# Breadboard_Power_Supply_-_SMD.net
KiCad netlist of a schematic drawn in EAGLE
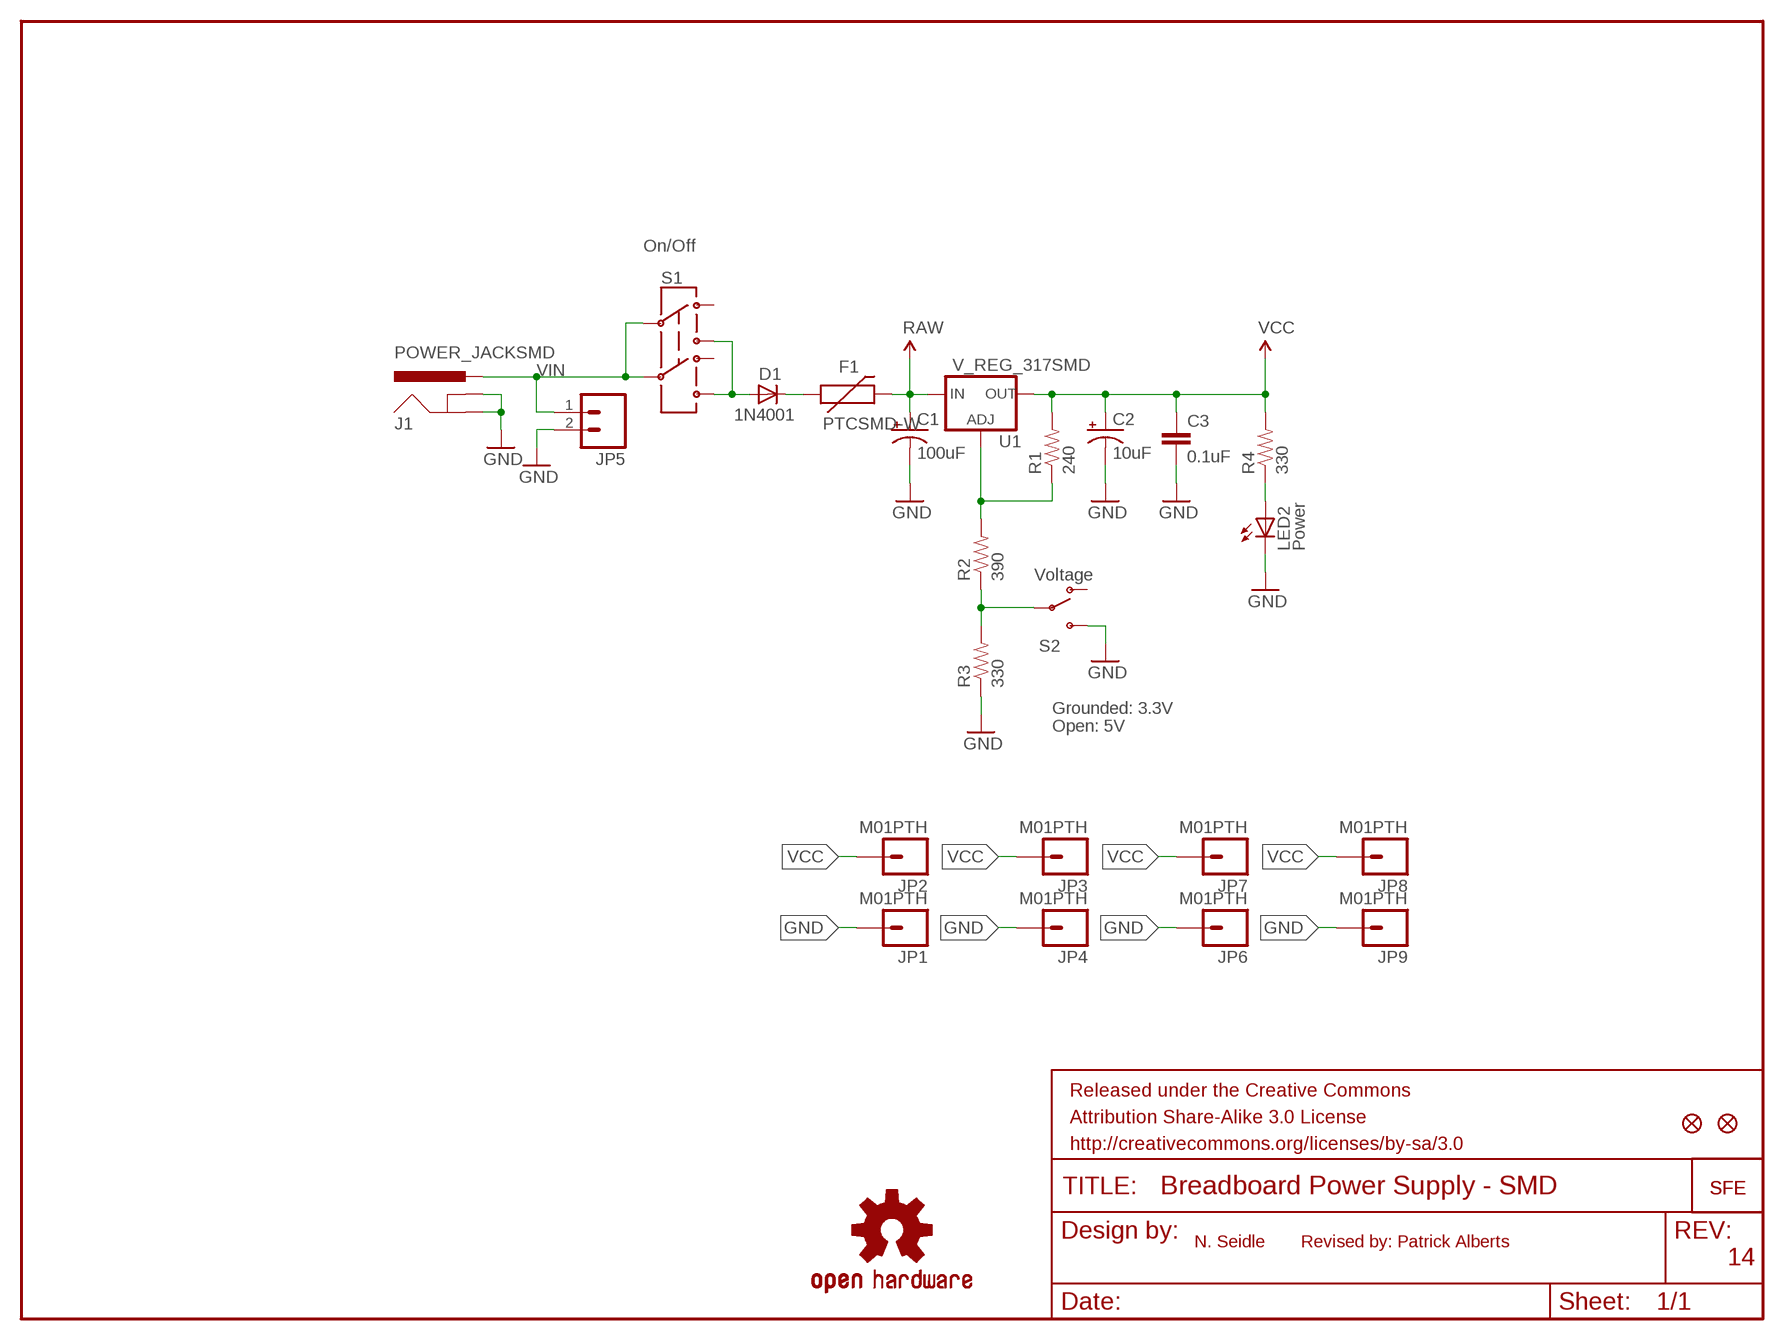
[diagram p0: schematic, sheet 1]

(export (version "E")
  (design (tool "Eeschema 10.0.6"))
  (components
    (comp (ref "C1")
      (value "100uF")
      (footprint "eagle-import:EIA7343")
      (libsource (lib "eagle-import") (part "CAP_POL7343"))
    )
    (comp (ref "C2")
      (value "10uF")
      (footprint "eagle-import:EIA3216")
      (libsource (lib "eagle-import") (part "CAP_POL1206"))
    )
    (comp (ref "C3")
      (value "0.1uF")
      (footprint "eagle-import:0603-CAP")
      (libsource (lib "eagle-import") (part "CAP0603-CAP"))
    )
    (comp (ref "D1")
      (value "1N4001")
      (footprint "eagle-import:SMA-DIODE-TYLERALT1")
      (libsource (lib "eagle-import") (part "DIODESMA-TYLERALT1"))
    )
    (comp (ref "F1")
      (value "PTCSMD-W")
      (footprint "eagle-import:PTC-1206-WIDE")
      (libsource (lib "eagle-import") (part "PTCSMD-W"))
    )
    (comp (ref "FRAME1")
      (value "FRAME-LETTER")
      (footprint "eagle-import:CREATIVE_COMMONS")
      (libsource (lib "eagle-import") (part "FRAME-LETTER"))
    )
    (comp (ref "J1")
      (value "POWER_JACKSMD")
      (footprint "eagle-import:POWER_JACK_SMD")
      (libsource (lib "eagle-import") (part "POWER_JACKSMD"))
    )
    (comp (ref "JP1")
      (value "M01PTH")
      (footprint "eagle-import:1X01")
      (libsource (lib "eagle-import") (part "M01PTH"))
    )
    (comp (ref "JP2")
      (value "M01PTH")
      (footprint "eagle-import:1X01")
      (libsource (lib "eagle-import") (part "M01PTH"))
    )
    (comp (ref "JP3")
      (value "M01PTH")
      (footprint "eagle-import:1X01")
      (libsource (lib "eagle-import") (part "M01PTH"))
    )
    (comp (ref "JP4")
      (value "M01PTH")
      (footprint "eagle-import:1X01")
      (libsource (lib "eagle-import") (part "M01PTH"))
    )
    (comp (ref "JP5")
      (value "M02PTH")
      (footprint "eagle-import:1X02")
      (libsource (lib "eagle-import") (part "M02PTH"))
    )
    (comp (ref "JP6")
      (value "M01PTH")
      (footprint "eagle-import:1X01")
      (libsource (lib "eagle-import") (part "M01PTH"))
    )
    (comp (ref "JP7")
      (value "M01PTH")
      (footprint "eagle-import:1X01")
      (libsource (lib "eagle-import") (part "M01PTH"))
    )
    (comp (ref "JP8")
      (value "M01PTH")
      (footprint "eagle-import:1X01")
      (libsource (lib "eagle-import") (part "M01PTH"))
    )
    (comp (ref "JP9")
      (value "M01PTH")
      (footprint "eagle-import:1X01")
      (libsource (lib "eagle-import") (part "M01PTH"))
    )
    (comp (ref "LED2")
      (value "Power")
      (footprint "eagle-import:LED-1206")
      (libsource (lib "eagle-import") (part "LED1206"))
    )
    (comp (ref "LOGO1")
      (value "OSHW-LOGOS")
      (footprint "eagle-import:OSHW-LOGO-S")
      (libsource (lib "eagle-import") (part "OSHW-LOGOS"))
    )
    (comp (ref "R1")
      (value "240")
      (footprint "eagle-import:0603-RES")
      (libsource (lib "eagle-import") (part "RESISTOR0603-RES"))
    )
    (comp (ref "R2")
      (value "390")
      (footprint "eagle-import:0603-RES")
      (libsource (lib "eagle-import") (part "RESISTOR0603-RES"))
    )
    (comp (ref "R3")
      (value "330")
      (footprint "eagle-import:0603-RES")
      (libsource (lib "eagle-import") (part "RESISTOR0603-RES"))
    )
    (comp (ref "R4")
      (value "330")
      (footprint "eagle-import:0603-RES")
      (libsource (lib "eagle-import") (part "RESISTOR0603-RES"))
    )
    (comp (ref "S1")
      (value "On/Off")
      (footprint "eagle-import:AYZ0202")
      (libsource (lib "eagle-import") (part "AYZ0202"))
    )
    (comp (ref "S2")
      (value "Voltage")
      (footprint "eagle-import:AYZ0202")
      (libsource (lib "eagle-import") (part "SWITCH-SPSTSMD"))
    )
    (comp (ref "U$1")
      (value "LOGO-SFESK")
      (footprint "eagle-import:SFE-LOGO-FLAME")
      (libsource (lib "eagle-import") (part "LOGO-SFESK"))
    )
    (comp (ref "U$2")
      (value "LOGO-SFENEW")
      (footprint "eagle-import:SFE-NEW-WEBLOGO")
      (libsource (lib "eagle-import") (part "LOGO-SFENEW"))
    )
    (comp (ref "U$3")
      (value "FIDUCIAL1X2")
      (footprint "eagle-import:FIDUCIAL-1X2")
      (libsource (lib "eagle-import") (part "FIDUCIAL1X2"))
    )
    (comp (ref "U$4")
      (value "FIDUCIAL1X2")
      (footprint "eagle-import:FIDUCIAL-1X2")
      (libsource (lib "eagle-import") (part "FIDUCIAL1X2"))
    )
    (comp (ref "U1")
      (value "V_REG_317SMD")
      (footprint "eagle-import:SOT223")
      (libsource (lib "eagle-import") (part "V_REG_317SMD"))
    )
  )
  (nets
    (net (code "1") (name "/VIN") (class "Default")
      (node (ref "J1") (pin "VIN0") (pinfunction "PWR_VIN0") (pintype "bidirectional"))
      (node (ref "JP5") (pin "1") (pinfunction "1_1") (pintype "passive"))
      (node (ref "S1") (pin "2") (pinfunction "2_2") (pintype "bidirectional"))
      (node (ref "S1") (pin "5") (pinfunction "5_5") (pintype "bidirectional"))
    )
    (net (code "2") (name "GND") (class "Default")
      (node (ref "C1") (pin "C") (pinfunction "-_C") (pintype "passive"))
      (node (ref "C2") (pin "C") (pinfunction "-_C") (pintype "passive"))
      (node (ref "C3") (pin "2") (pinfunction "2_2") (pintype "passive"))
      (node (ref "J1") (pin "GND") (pinfunction "GNDBREAK_GND") (pintype "bidirectional"))
      (node (ref "J1") (pin "P$4") (pinfunction "GND_P$4") (pintype "bidirectional"))
      (node (ref "JP1") (pin "1") (pinfunction "1_1") (pintype "passive"))
      (node (ref "JP4") (pin "1") (pinfunction "1_1") (pintype "passive"))
      (node (ref "JP5") (pin "2") (pinfunction "2_2") (pintype "passive"))
      (node (ref "JP6") (pin "1") (pinfunction "1_1") (pintype "passive"))
      (node (ref "JP9") (pin "1") (pinfunction "1_1") (pintype "passive"))
      (node (ref "LED2") (pin "C") (pinfunction "C_C") (pintype "passive"))
      (node (ref "R3") (pin "1") (pinfunction "1_1") (pintype "passive"))
      (node (ref "S2") (pin "3") (pinfunction "S_3") (pintype "passive"))
    )
    (net (code "3") (name "Net-(D1-PadC)") (class "Default")
      (node (ref "D1") (pin "C") (pinfunction "C_C") (pintype "passive"))
      (node (ref "F1") (pin "1") (pinfunction "1_1") (pintype "bidirectional"))
    )
    (net (code "4") (name "Net-(LED2-PadA)") (class "Default")
      (node (ref "LED2") (pin "A") (pinfunction "A_A") (pintype "passive"))
      (node (ref "R4") (pin "1") (pinfunction "1_1") (pintype "passive"))
    )
    (net (code "5") (name "Net-(S1-3)") (class "Default")
      (node (ref "D1") (pin "A") (pinfunction "A_A") (pintype "passive"))
      (node (ref "S1") (pin "1") (pinfunction "3_1") (pintype "bidirectional"))
      (node (ref "S1") (pin "4") (pinfunction "6_4") (pintype "bidirectional"))
    )
    (net (code "6") (name "Net-(S2-P)") (class "Default")
      (node (ref "R2") (pin "1") (pinfunction "1_1") (pintype "passive"))
      (node (ref "R3") (pin "2") (pinfunction "2_2") (pintype "passive"))
      (node (ref "S2") (pin "2") (pinfunction "P_2") (pintype "passive"))
    )
    (net (code "7") (name "Net-(U1-ADJ)") (class "Default")
      (node (ref "R1") (pin "1") (pinfunction "1_1") (pintype "passive"))
      (node (ref "R2") (pin "2") (pinfunction "2_2") (pintype "passive"))
      (node (ref "U1") (pin "1") (pinfunction "ADJ_1") (pintype "input"))
    )
    (net (code "8") (name "RAW") (class "Default")
      (node (ref "C1") (pin "A") (pinfunction "+_A") (pintype "passive"))
      (node (ref "F1") (pin "2") (pinfunction "2_2") (pintype "bidirectional"))
      (node (ref "U1") (pin "3") (pinfunction "IN_3") (pintype "input"))
    )
    (net (code "9") (name "VCC") (class "Default")
      (node (ref "C2") (pin "A") (pinfunction "+_A") (pintype "passive"))
      (node (ref "C3") (pin "1") (pinfunction "1_1") (pintype "passive"))
      (node (ref "JP2") (pin "1") (pinfunction "1_1") (pintype "passive"))
      (node (ref "JP3") (pin "1") (pinfunction "1_1") (pintype "passive"))
      (node (ref "JP7") (pin "1") (pinfunction "1_1") (pintype "passive"))
      (node (ref "JP8") (pin "1") (pinfunction "1_1") (pintype "passive"))
      (node (ref "R1") (pin "2") (pinfunction "2_2") (pintype "passive"))
      (node (ref "R4") (pin "2") (pinfunction "2_2") (pintype "passive"))
      (node (ref "U1") (pin "2") (pinfunction "OUT_2") (pintype "output"))
    )
    (net (code "10") (name "unconnected-(S1-1-Pad3)") (class "Default")
      (node (ref "S1") (pin "3") (pinfunction "1_3") (pintype "bidirectional"))
    )
    (net (code "11") (name "unconnected-(S1-4-Pad6)") (class "Default")
      (node (ref "S1") (pin "6") (pinfunction "4_6") (pintype "bidirectional"))
    )
    (net (code "12") (name "unconnected-(S2-O-Pad1)") (class "Default")
      (node (ref "S2") (pin "1") (pinfunction "O_1") (pintype "passive"))
    )
  )
)
